# Rev2.net
KiCad netlist of a schematic drawn in EAGLE
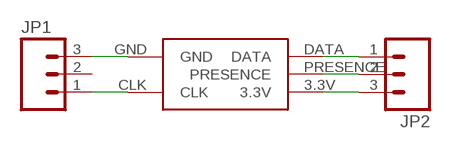
[diagram p0: schematic, sheet 1]

(export (version "E")
  (design (tool "Eeschema 10.0.6"))
  (components
    (comp (ref "JP1")
      (value "M03PTH")
      (footprint "eagle-import:1X03")
      (libsource (lib "eagle-import") (part "M03PTH"))
    )
    (comp (ref "JP2")
      (value "M03PTH")
      (footprint "eagle-import:1X03")
      (libsource (lib "eagle-import") (part "M03PTH"))
    )
    (comp (ref "U$1")
      (value "NUNCHUCKLOCL")
      (footprint "eagle-import:NUNCHUCK-LOCK")
      (libsource (lib "eagle-import") (part "NUNCHUCKLOCL"))
    )
  )
  (nets
    (net (code "1") (name "Net-(JP1-Pad1)") (class "Default")
      (node (ref "JP1") (pin "1") (pinfunction "1_1") (pintype "passive"))
      (node (ref "U$1") (pin "CLK") (pinfunction "CLK_CLK") (pintype "bidirectional"))
    )
    (net (code "2") (name "Net-(JP1-Pad3)") (class "Default")
      (node (ref "JP1") (pin "3") (pinfunction "3_3") (pintype "passive"))
      (node (ref "U$1") (pin "GND") (pinfunction "GND_GND") (pintype "bidirectional"))
    )
    (net (code "3") (name "Net-(JP2-Pad1)") (class "Default")
      (node (ref "JP2") (pin "1") (pinfunction "1_1") (pintype "passive"))
      (node (ref "U$1") (pin "DATA") (pinfunction "DATA_DATA") (pintype "bidirectional"))
    )
    (net (code "4") (name "Net-(JP2-Pad2)") (class "Default")
      (node (ref "JP2") (pin "2") (pinfunction "2_2") (pintype "passive"))
      (node (ref "U$1") (pin "PRESENCE") (pinfunction "PRESENCE_PRESENCE") (pintype "bidirectional"))
    )
    (net (code "5") (name "Net-(JP2-Pad3)") (class "Default")
      (node (ref "JP2") (pin "3") (pinfunction "3_3") (pintype "passive"))
      (node (ref "U$1") (pin "3.3V") (pinfunction "3.3V_3.3V") (pintype "bidirectional"))
    )
    (net (code "6") (name "unconnected-(JP1-Pad2)") (class "Default")
      (node (ref "JP1") (pin "2") (pinfunction "2_2") (pintype "passive"))
    )
  )
)
